# Main_PCB.net
KiCad netlist of a schematic drawn in EAGLE
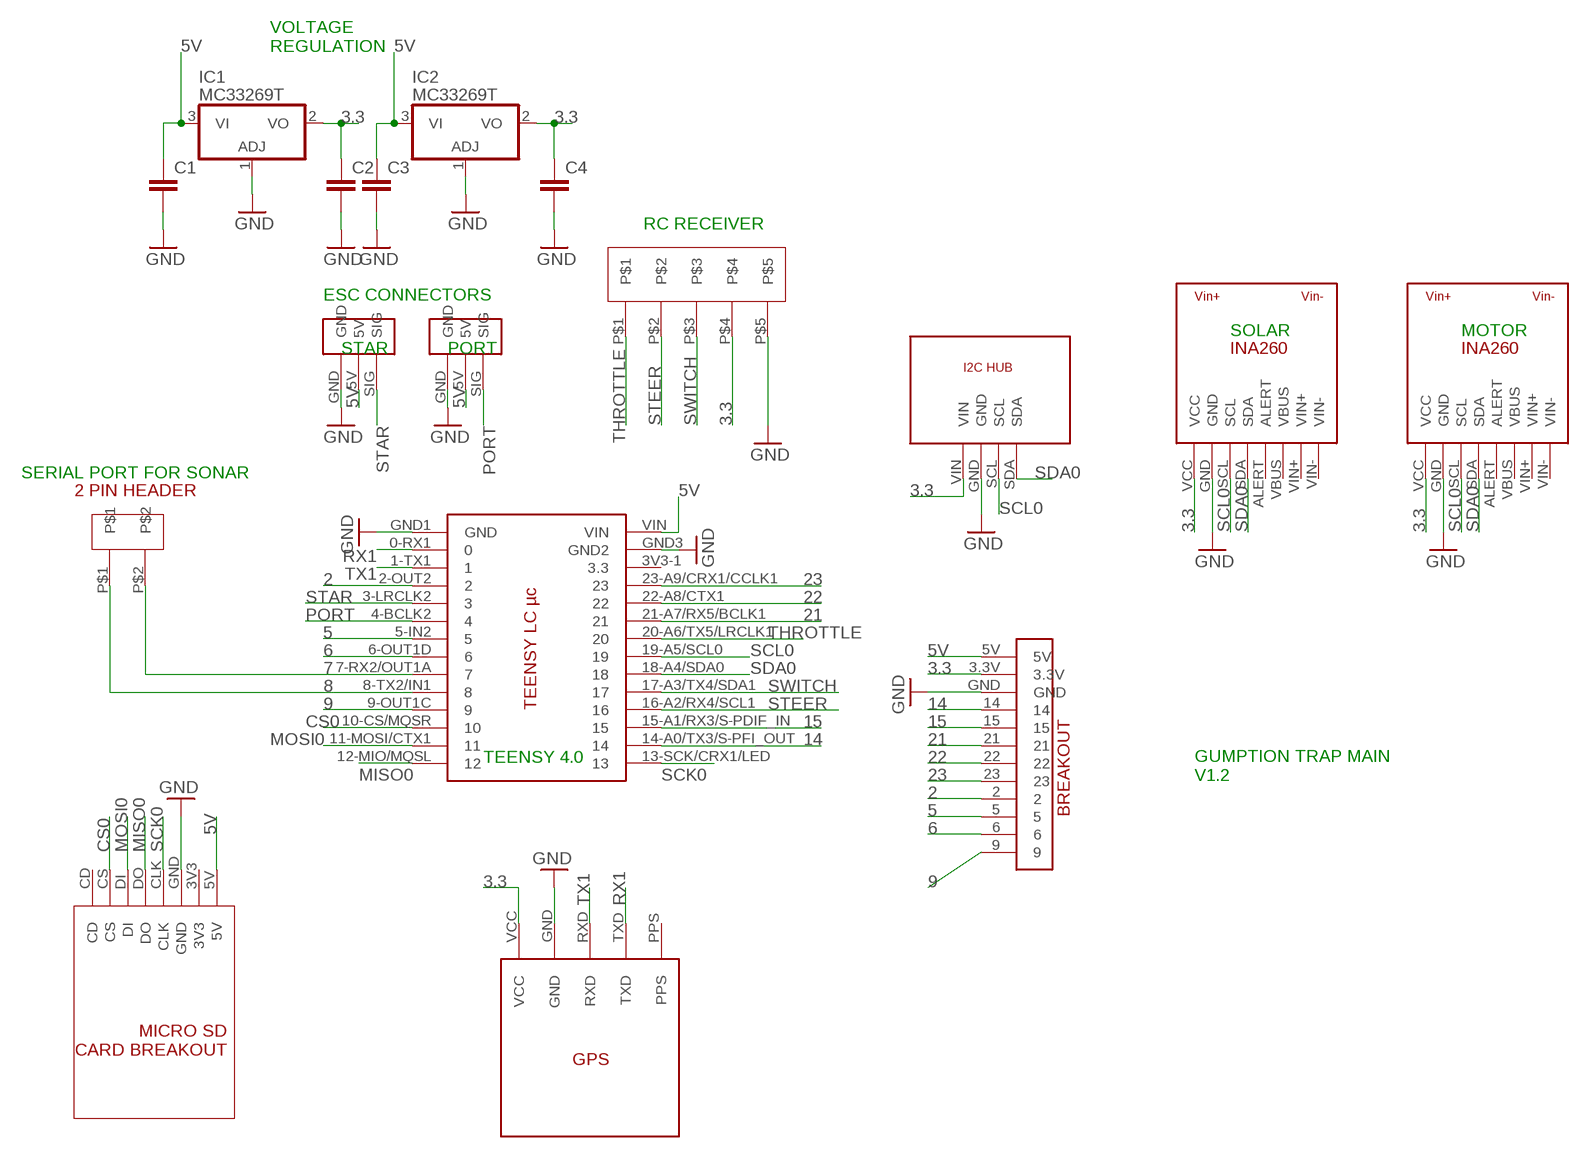
[diagram p0: schematic, sheet 1]

(export (version "E")
  (design (tool "Eeschema 10.0.6"))
  (components
    (comp (ref "C1")
      (value "C2.5/2")
      (footprint "eagle-import:C2.5-2")
      (libsource (lib "eagle-import") (part "C2.5/2"))
    )
    (comp (ref "C2")
      (value "C2.5/2")
      (footprint "eagle-import:C2.5-2")
      (libsource (lib "eagle-import") (part "C2.5/2"))
    )
    (comp (ref "C3")
      (value "C2.5/2")
      (footprint "eagle-import:C2.5-2")
      (libsource (lib "eagle-import") (part "C2.5/2"))
    )
    (comp (ref "C4")
      (value "C2.5/2")
      (footprint "eagle-import:C2.5-2")
      (libsource (lib "eagle-import") (part "C2.5/2"))
    )
    (comp (ref "IC1")
      (value "MC33269T")
      (footprint "eagle-import:TO220V")
      (libsource (lib "eagle-import") (part "MC33269?T"))
    )
    (comp (ref "IC2")
      (value "MC33269T")
      (footprint "eagle-import:TO220V")
      (libsource (lib "eagle-import") (part "MC33269?T"))
    )
    (comp (ref "MOTOR")
      (value "INA260")
      (footprint "eagle-import:INA260")
      (libsource (lib "eagle-import") (part "INA260"))
    )
    (comp (ref "PORT")
      (value "SERVO3PIN")
      (footprint "eagle-import:SERVO3PIN")
      (libsource (lib "eagle-import") (part "SERVO3PIN"))
    )
    (comp (ref "SOLAR")
      (value "INA260")
      (footprint "eagle-import:INA260")
      (libsource (lib "eagle-import") (part "INA260"))
    )
    (comp (ref "STAR")
      (value "SERVO3PIN")
      (footprint "eagle-import:SERVO3PIN")
      (libsource (lib "eagle-import") (part "SERVO3PIN"))
    )
    (comp (ref "U$1")
      (value "TEENSYLC")
      (footprint "eagle-import:TEENSY40")
      (libsource (lib "eagle-import") (part "TEENSYLC"))
    )
    (comp (ref "U$2")
      (value "GPS")
      (footprint "eagle-import:GPS")
      (libsource (lib "eagle-import") (part "GPS"))
    )
    (comp (ref "U$3")
      (value "QT5HUB")
      (footprint "eagle-import:QT5HUB")
      (libsource (lib "eagle-import") (part "QT5HUB"))
    )
    (comp (ref "U$4")
      (value "SD2")
      (footprint "eagle-import:SD2")
      (libsource (lib "eagle-import") (part "SD2"))
    )
    (comp (ref "U$5")
      (value "2PIN_JST-XH")
      (footprint "eagle-import:2PIN_JST-XH")
      (libsource (lib "eagle-import") (part "2PIN_JST-XH"))
    )
    (comp (ref "U$6")
      (value "5PIN_JST-XH")
      (footprint "eagle-import:5PIN_JST-XH")
      (libsource (lib "eagle-import") (part "5PIN_JST-XH"))
    )
    (comp (ref "U$8")
      (value "BREAKOUT")
      (footprint "eagle-import:BREAKOUT")
      (libsource (lib "eagle-import") (part "BREAKOUT"))
    )
  )
  (nets
    (net (code "1") (name "/2") (class "Default")
      (node (ref "U$1") (pin "2-OUT2") (pinfunction "2_2-OUT2") (pintype "bidirectional"))
      (node (ref "U$8") (pin "2") (pinfunction "2_2") (pintype "bidirectional"))
    )
    (net (code "2") (name "/3.3") (class "Default")
      (node (ref "C2") (pin "1") (pinfunction "1_1") (pintype "passive"))
      (node (ref "C4") (pin "1") (pinfunction "1_1") (pintype "passive"))
      (node (ref "IC1") (pin "2") (pinfunction "VO_2") (pintype "passive"))
      (node (ref "IC2") (pin "2") (pinfunction "VO_2") (pintype "passive"))
      (node (ref "MOTOR") (pin "VCC") (pinfunction "VCC_VCC") (pintype "bidirectional"))
      (node (ref "SOLAR") (pin "VCC") (pinfunction "VCC_VCC") (pintype "bidirectional"))
      (node (ref "U$2") (pin "VCC") (pinfunction "VCC_VCC") (pintype "bidirectional"))
      (node (ref "U$3") (pin "VIN") (pinfunction "VIN_VIN") (pintype "bidirectional"))
      (node (ref "U$6") (pin "P$4") (pinfunction "P$4_P$4") (pintype "bidirectional"))
      (node (ref "U$8") (pin "3.3V") (pinfunction "3.3V_3.3V") (pintype "bidirectional"))
    )
    (net (code "3") (name "/5") (class "Default")
      (node (ref "U$1") (pin "5-IN2") (pinfunction "5_5-IN2") (pintype "bidirectional"))
      (node (ref "U$8") (pin "5") (pinfunction "5_5") (pintype "bidirectional"))
    )
    (net (code "4") (name "/5V") (class "Default")
      (node (ref "C1") (pin "1") (pinfunction "1_1") (pintype "passive"))
      (node (ref "C3") (pin "1") (pinfunction "1_1") (pintype "passive"))
      (node (ref "IC1") (pin "3") (pinfunction "VI_3") (pintype "input"))
      (node (ref "IC2") (pin "3") (pinfunction "VI_3") (pintype "input"))
      (node (ref "PORT") (pin "5V") (pinfunction "5V_5V") (pintype "bidirectional"))
      (node (ref "STAR") (pin "5V") (pinfunction "5V_5V") (pintype "bidirectional"))
      (node (ref "U$1") (pin "VIN") (pinfunction "VIN_VIN") (pintype "bidirectional"))
      (node (ref "U$4") (pin "5V") (pinfunction "5V_5V") (pintype "bidirectional"))
      (node (ref "U$8") (pin "5V") (pinfunction "5V_5V") (pintype "bidirectional"))
    )
    (net (code "5") (name "/6") (class "Default")
      (node (ref "U$1") (pin "6-OUT1D") (pinfunction "6_6-OUT1D") (pintype "bidirectional"))
      (node (ref "U$8") (pin "6") (pinfunction "6_6") (pintype "bidirectional"))
    )
    (net (code "6") (name "/7") (class "Default")
      (node (ref "U$1") (pin "7-RX2/OUT1A") (pinfunction "7_7-RX2/OUT1A") (pintype "bidirectional"))
      (node (ref "U$5") (pin "P$2") (pinfunction "P$2_P$2") (pintype "bidirectional"))
    )
    (net (code "7") (name "/8") (class "Default")
      (node (ref "U$1") (pin "8-TX2/IN1") (pinfunction "8_8-TX2/IN1") (pintype "bidirectional"))
      (node (ref "U$5") (pin "P$1") (pinfunction "P$1_P$1") (pintype "bidirectional"))
    )
    (net (code "8") (name "/9") (class "Default")
      (node (ref "U$1") (pin "9-OUT1C") (pinfunction "9_9-OUT1C") (pintype "bidirectional"))
      (node (ref "U$8") (pin "9") (pinfunction "9_9") (pintype "bidirectional"))
    )
    (net (code "9") (name "/14") (class "Default")
      (node (ref "U$1") (pin "14-A0/TX3/S-PFI_OUT") (pinfunction "14_14-A0/TX3/S-PFI_OUT") (pintype "bidirectional"))
      (node (ref "U$8") (pin "14") (pinfunction "14_14") (pintype "bidirectional"))
    )
    (net (code "10") (name "/15") (class "Default")
      (node (ref "U$1") (pin "15-A1/RX3/S-PDIF_IN") (pinfunction "15_15-A1/RX3/S-PDIF_IN") (pintype "bidirectional"))
      (node (ref "U$8") (pin "15") (pinfunction "15_15") (pintype "bidirectional"))
    )
    (net (code "11") (name "/21") (class "Default")
      (node (ref "U$1") (pin "21-A7/RX5/BCLK1") (pinfunction "21_21-A7/RX5/BCLK1") (pintype "bidirectional"))
      (node (ref "U$8") (pin "21") (pinfunction "21_21") (pintype "bidirectional"))
    )
    (net (code "12") (name "/22") (class "Default")
      (node (ref "U$1") (pin "22-A8/CTX1") (pinfunction "22_22-A8/CTX1") (pintype "bidirectional"))
      (node (ref "U$8") (pin "22") (pinfunction "22_22") (pintype "bidirectional"))
    )
    (net (code "13") (name "/23") (class "Default")
      (node (ref "U$1") (pin "23-A9/CRX1/CCLK1") (pinfunction "23_23-A9/CRX1/CCLK1") (pintype "bidirectional"))
      (node (ref "U$8") (pin "23") (pinfunction "23_23") (pintype "bidirectional"))
    )
    (net (code "14") (name "/CS0") (class "Default")
      (node (ref "U$1") (pin "10-CS/MQSR") (pinfunction "10_10-CS/MQSR") (pintype "bidirectional"))
      (node (ref "U$4") (pin "CS") (pinfunction "CS_CS") (pintype "bidirectional"))
    )
    (net (code "15") (name "/MISO0") (class "Default")
      (node (ref "U$1") (pin "12-MIO/MQSL") (pinfunction "12_12-MIO/MQSL") (pintype "bidirectional"))
      (node (ref "U$4") (pin "DO") (pinfunction "DO_DO") (pintype "bidirectional"))
    )
    (net (code "16") (name "/MOSI0") (class "Default")
      (node (ref "U$1") (pin "11-MOSI/CTX1") (pinfunction "11_11-MOSI/CTX1") (pintype "bidirectional"))
      (node (ref "U$4") (pin "DI") (pinfunction "DI_DI") (pintype "bidirectional"))
    )
    (net (code "17") (name "/PORT") (class "Default")
      (node (ref "PORT") (pin "SIG") (pinfunction "SIG_SIG") (pintype "bidirectional"))
      (node (ref "U$1") (pin "4-BCLK2") (pinfunction "4_4-BCLK2") (pintype "bidirectional"))
    )
    (net (code "18") (name "/RX1") (class "Default")
      (node (ref "U$1") (pin "0-RX1") (pinfunction "0_0-RX1") (pintype "bidirectional"))
      (node (ref "U$2") (pin "TXD") (pinfunction "TXD_TXD") (pintype "bidirectional"))
    )
    (net (code "19") (name "/SCK0") (class "Default")
      (node (ref "U$1") (pin "13-SCK/CRX1/LED") (pinfunction "13_13-SCK/CRX1/LED") (pintype "bidirectional"))
      (node (ref "U$4") (pin "CLK") (pinfunction "CLK_CLK") (pintype "bidirectional"))
    )
    (net (code "20") (name "/SCL0") (class "Default")
      (node (ref "MOTOR") (pin "SCL") (pinfunction "SCL_SCL") (pintype "bidirectional"))
      (node (ref "SOLAR") (pin "SCL") (pinfunction "SCL_SCL") (pintype "bidirectional"))
      (node (ref "U$1") (pin "19-A5/SCL0") (pinfunction "19_19-A5/SCL0") (pintype "bidirectional"))
      (node (ref "U$3") (pin "SCL") (pinfunction "SCL_SCL") (pintype "bidirectional"))
    )
    (net (code "21") (name "/SDA0") (class "Default")
      (node (ref "MOTOR") (pin "SDA") (pinfunction "SDA_SDA") (pintype "bidirectional"))
      (node (ref "SOLAR") (pin "SDA") (pinfunction "SDA_SDA") (pintype "bidirectional"))
      (node (ref "U$1") (pin "18-A4/SDA0") (pinfunction "18_18-A4/SDA0") (pintype "bidirectional"))
      (node (ref "U$3") (pin "SDA") (pinfunction "SDA_SDA") (pintype "bidirectional"))
    )
    (net (code "22") (name "/STAR") (class "Default")
      (node (ref "STAR") (pin "SIG") (pinfunction "SIG_SIG") (pintype "bidirectional"))
      (node (ref "U$1") (pin "3-LRCLK2") (pinfunction "3_3-LRCLK2") (pintype "bidirectional"))
    )
    (net (code "23") (name "/STEER") (class "Default")
      (node (ref "U$1") (pin "16-A2/RX4/SCL1") (pinfunction "16_16-A2/RX4/SCL1") (pintype "bidirectional"))
      (node (ref "U$6") (pin "P$2") (pinfunction "P$2_P$2") (pintype "bidirectional"))
    )
    (net (code "24") (name "/SWITCH") (class "Default")
      (node (ref "U$1") (pin "17-A3/TX4/SDA1") (pinfunction "17_17-A3/TX4/SDA1") (pintype "bidirectional"))
      (node (ref "U$6") (pin "P$3") (pinfunction "P$3_P$3") (pintype "bidirectional"))
    )
    (net (code "25") (name "/THROTTLE") (class "Default")
      (node (ref "U$1") (pin "20-A6/TX5/LRCLK1") (pinfunction "20_20-A6/TX5/LRCLK1") (pintype "bidirectional"))
      (node (ref "U$6") (pin "P$1") (pinfunction "P$1_P$1") (pintype "bidirectional"))
    )
    (net (code "26") (name "/TX1") (class "Default")
      (node (ref "U$1") (pin "1-TX1") (pinfunction "1_1-TX1") (pintype "bidirectional"))
      (node (ref "U$2") (pin "RXD") (pinfunction "RXD_RXD") (pintype "bidirectional"))
    )
    (net (code "27") (name "GND") (class "Default")
      (node (ref "C1") (pin "2") (pinfunction "2_2") (pintype "passive"))
      (node (ref "C2") (pin "2") (pinfunction "2_2") (pintype "passive"))
      (node (ref "C3") (pin "2") (pinfunction "2_2") (pintype "passive"))
      (node (ref "C4") (pin "2") (pinfunction "2_2") (pintype "passive"))
      (node (ref "IC1") (pin "1") (pinfunction "ADJ_1") (pintype "input"))
      (node (ref "IC2") (pin "1") (pinfunction "ADJ_1") (pintype "input"))
      (node (ref "MOTOR") (pin "GND") (pinfunction "GND_GND") (pintype "bidirectional"))
      (node (ref "PORT") (pin "GND") (pinfunction "GND_GND") (pintype "bidirectional"))
      (node (ref "SOLAR") (pin "GND") (pinfunction "GND_GND") (pintype "bidirectional"))
      (node (ref "STAR") (pin "GND") (pinfunction "GND_GND") (pintype "bidirectional"))
      (node (ref "U$1") (pin "GND1") (pinfunction "GND_GND1") (pintype "bidirectional"))
      (node (ref "U$1") (pin "GND3") (pinfunction "GND2_GND3") (pintype "bidirectional"))
      (node (ref "U$2") (pin "GND") (pinfunction "GND_GND") (pintype "bidirectional"))
      (node (ref "U$3") (pin "GND") (pinfunction "GND_GND") (pintype "bidirectional"))
      (node (ref "U$4") (pin "GND") (pinfunction "GND_GND") (pintype "bidirectional"))
      (node (ref "U$6") (pin "P$5") (pinfunction "P$5_P$5") (pintype "bidirectional"))
      (node (ref "U$8") (pin "GND") (pinfunction "GND_GND") (pintype "bidirectional"))
    )
    (net (code "28") (name "unconnected-(MOTOR-PadALERT)") (class "Default")
      (node (ref "MOTOR") (pin "ALERT") (pinfunction "ALERT_ALERT") (pintype "bidirectional"))
    )
    (net (code "29") (name "unconnected-(MOTOR-PadVBUS)") (class "Default")
      (node (ref "MOTOR") (pin "VBUS") (pinfunction "VBUS_VBUS") (pintype "bidirectional"))
    )
    (net (code "30") (name "unconnected-(MOTOR-PadVIN+)") (class "Default")
      (node (ref "MOTOR") (pin "VIN+") (pinfunction "VIN+_VIN+") (pintype "bidirectional"))
    )
    (net (code "31") (name "unconnected-(MOTOR-PadVIN-)") (class "Default")
      (node (ref "MOTOR") (pin "VIN-") (pinfunction "VIN-_VIN-") (pintype "bidirectional"))
    )
    (net (code "32") (name "unconnected-(SOLAR-PadALERT)") (class "Default")
      (node (ref "SOLAR") (pin "ALERT") (pinfunction "ALERT_ALERT") (pintype "bidirectional"))
    )
    (net (code "33") (name "unconnected-(SOLAR-PadVBUS)") (class "Default")
      (node (ref "SOLAR") (pin "VBUS") (pinfunction "VBUS_VBUS") (pintype "bidirectional"))
    )
    (net (code "34") (name "unconnected-(SOLAR-PadVIN+)") (class "Default")
      (node (ref "SOLAR") (pin "VIN+") (pinfunction "VIN+_VIN+") (pintype "bidirectional"))
    )
    (net (code "35") (name "unconnected-(SOLAR-PadVIN-)") (class "Default")
      (node (ref "SOLAR") (pin "VIN-") (pinfunction "VIN-_VIN-") (pintype "bidirectional"))
    )
    (net (code "36") (name "unconnected-(U$1-3.3-Pad3V3-1)") (class "Default")
      (node (ref "U$1") (pin "3V3-1") (pinfunction "3.3_3V3-1") (pintype "bidirectional"))
    )
    (net (code "37") (name "unconnected-(U$2-PadPPS)") (class "Default")
      (node (ref "U$2") (pin "PPS") (pinfunction "PPS_PPS") (pintype "bidirectional"))
    )
    (net (code "38") (name "unconnected-(U$4-Pad3V3)") (class "Default")
      (node (ref "U$4") (pin "3V3") (pinfunction "3V3_3V3") (pintype "bidirectional"))
    )
    (net (code "39") (name "unconnected-(U$4-PadCD)") (class "Default")
      (node (ref "U$4") (pin "CD") (pinfunction "CD_CD") (pintype "bidirectional"))
    )
  )
)
